# amigaDIP40_2025-07-20.net
KiCad netlist of a schematic drawn in Altium Designer
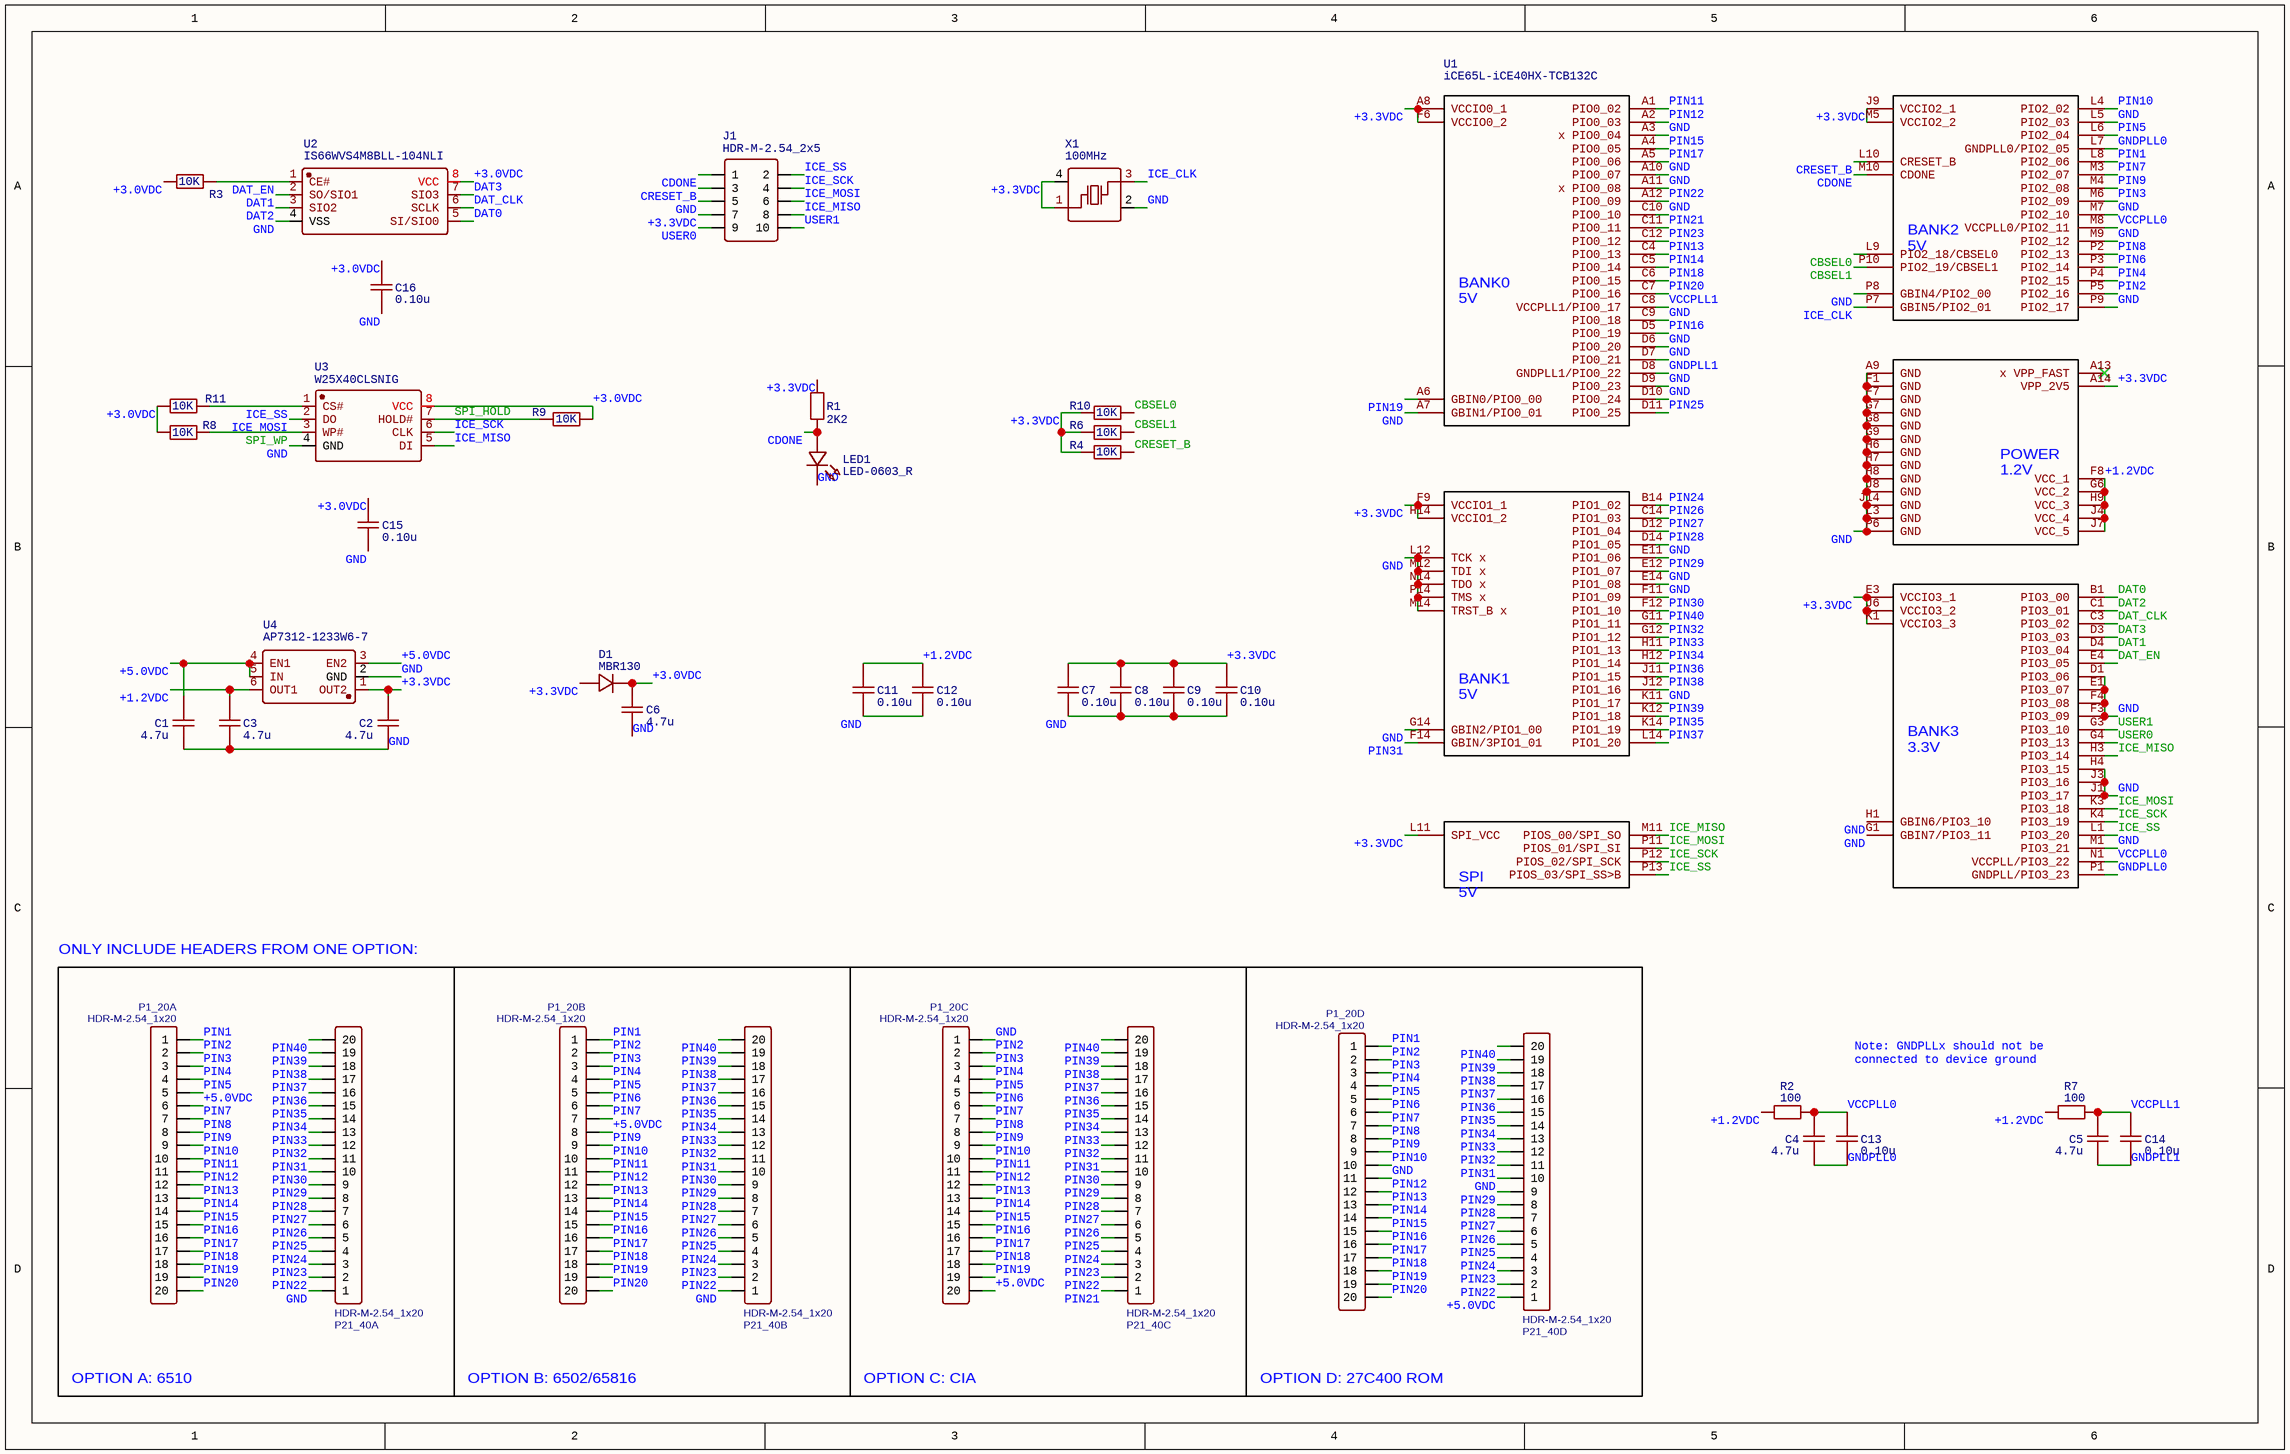
[diagram p0: amigaDIP40_2025-07-20.schdoc]

(export (version "E")
  (design (tool "Eeschema 10.0.6"))
  (components
    (comp (ref "C1")
      (value "4.7u")
      (fields
        (field (name "MANUFACTURER PART") "GCM21BR71E105KA56L")
        (field (name "MANUFACTURER") "MuRata")
        (field (name "CONTRIBUTOR") "LCEDA_Lib")
      )
      (libsource (lib "altium-import") (part "root_1_4.7u_"))
    )
    (comp (ref "C2")
      (value "4.7u")
      (fields
        (field (name "MANUFACTURER PART") "GCM21BR71E105KA56L")
        (field (name "MANUFACTURER") "MuRata")
        (field (name "CONTRIBUTOR") "LCEDA_Lib")
      )
      (libsource (lib "altium-import") (part "root_1_4.7u_"))
    )
    (comp (ref "C3")
      (value "4.7u")
      (fields
        (field (name "MANUFACTURER PART") "GCM21BR71E105KA56L")
        (field (name "MANUFACTURER") "MuRata")
        (field (name "CONTRIBUTOR") "LCEDA_Lib")
      )
      (libsource (lib "") (part "root_1_4.7u__1"))
    )
    (comp (ref "C4")
      (value "4.7u")
      (fields
        (field (name "MANUFACTURER PART") "GCM21BR71E105KA56L")
        (field (name "MANUFACTURER") "MuRata")
        (field (name "CONTRIBUTOR") "LCEDA_Lib")
      )
      (libsource (lib "altium-import") (part "root_1_4.7u_"))
    )
    (comp (ref "C5")
      (value "4.7u")
      (fields
        (field (name "MANUFACTURER PART") "GCM21BR71E105KA56L")
        (field (name "MANUFACTURER") "MuRata")
        (field (name "CONTRIBUTOR") "LCEDA_Lib")
      )
      (libsource (lib "altium-import") (part "root_1_4.7u_"))
    )
    (comp (ref "C6")
      (value "4.7u")
      (fields
        (field (name "MANUFACTURER PART") "GCM21BR71E105KA56L")
        (field (name "MANUFACTURER") "MuRata")
        (field (name "CONTRIBUTOR") "LCEDA_Lib")
      )
      (libsource (lib "") (part "root_1_4.7u__1"))
    )
    (comp (ref "C7")
      (value "0.10u")
      (fields
        (field (name "MANUFACTURER PART") "GRM188R71H104KA93D")
        (field (name "MANUFACTURER") "MuRata")
        (field (name "CONTRIBUTOR") "LCEDA_Lib")
      )
      (libsource (lib "altium-import") (part "root_1_0.10u_"))
    )
    (comp (ref "C8")
      (value "0.10u")
      (fields
        (field (name "MANUFACTURER PART") "GRM188R71H104KA93D")
        (field (name "MANUFACTURER") "MuRata")
        (field (name "CONTRIBUTOR") "LCEDA_Lib")
      )
      (libsource (lib "altium-import") (part "root_1_0.10u_"))
    )
    (comp (ref "C9")
      (value "0.10u")
      (fields
        (field (name "MANUFACTURER PART") "GRM188R71H104KA93D")
        (field (name "MANUFACTURER") "MuRata")
        (field (name "CONTRIBUTOR") "LCEDA_Lib")
      )
      (libsource (lib "altium-import") (part "root_1_0.10u_"))
    )
    (comp (ref "C10")
      (value "0.10u")
      (fields
        (field (name "MANUFACTURER PART") "GRM188R71H104KA93D")
        (field (name "MANUFACTURER") "MuRata")
        (field (name "CONTRIBUTOR") "LCEDA_Lib")
      )
      (libsource (lib "altium-import") (part "root_1_0.10u_"))
    )
    (comp (ref "C11")
      (value "0.10u")
      (fields
        (field (name "MANUFACTURER PART") "GRM188R71H104KA93D")
        (field (name "MANUFACTURER") "MuRata")
        (field (name "CONTRIBUTOR") "LCEDA_Lib")
      )
      (libsource (lib "altium-import") (part "root_1_0.10u_"))
    )
    (comp (ref "C12")
      (value "0.10u")
      (fields
        (field (name "MANUFACTURER PART") "GRM188R71H104KA93D")
        (field (name "MANUFACTURER") "MuRata")
        (field (name "CONTRIBUTOR") "LCEDA_Lib")
      )
      (libsource (lib "altium-import") (part "root_1_0.10u_"))
    )
    (comp (ref "C13")
      (value "0.10u")
      (fields
        (field (name "MANUFACTURER PART") "GRM188R71H104KA93D")
        (field (name "MANUFACTURER") "MuRata")
        (field (name "CONTRIBUTOR") "LCEDA_Lib")
      )
      (libsource (lib "altium-import") (part "root_1_0.10u_"))
    )
    (comp (ref "C14")
      (value "0.10u")
      (fields
        (field (name "MANUFACTURER PART") "GRM188R71H104KA93D")
        (field (name "MANUFACTURER") "MuRata")
        (field (name "CONTRIBUTOR") "LCEDA_Lib")
      )
      (libsource (lib "altium-import") (part "root_1_0.10u_"))
    )
    (comp (ref "C15")
      (value "0.10u")
      (fields
        (field (name "MANUFACTURER PART") "GRM188R71H104KA93D")
        (field (name "MANUFACTURER") "MuRata")
        (field (name "CONTRIBUTOR") "LCEDA_Lib")
      )
      (libsource (lib "altium-import") (part "root_1_0.10u_"))
    )
    (comp (ref "C16")
      (value "0.10u")
      (fields
        (field (name "MANUFACTURER PART") "GRM188R71H104KA93D")
        (field (name "MANUFACTURER") "MuRata")
        (field (name "CONTRIBUTOR") "LCEDA_Lib")
      )
      (libsource (lib "altium-import") (part "root_1_0.10u_"))
    )
    (comp (ref "D1")
      (value "MBR130")
      (fields (field (name "MANUFACTURER") "SK") (field (name "CONTRIBUTOR") "LCSC"))
      (libsource (lib "altium-import") (part "root_2_MBR130_"))
    )
    (comp (ref "J1")
      (value "HDR-M-2.54_2x5")
      (fields (field (name "CONTRIBUTOR") "LCEDA_Lib"))
      (libsource (lib "altium-import") (part "root_0_HDR-M-2.54_2x5_"))
    )
    (comp (ref "LED1")
      (value "LED-0603_R")
      (fields
        (field (name "MANUFACTURER") "EVERLIGHT(台湾亿光)")
        (field (name "MANUFACTURER PART") "19-217/R6C-AL1M2VY/3T")
        (field (name "CONTRIBUTOR") "LCEDA_01")
      )
      (libsource (lib "altium-import") (part "root_3_LED-0603_R_"))
    )
    (comp (ref "P1_20A")
      (value "HDR-M-2.54_1x20")
      (fields (field (name "CONTRIBUTOR") "LCEDA_Lib"))
      (libsource (lib "altium-import") (part "root_0_HDR-M-2.54_1x20_"))
    )
    (comp (ref "P1_20B")
      (value "HDR-M-2.54_1x20")
      (fields (field (name "CONTRIBUTOR") "LCEDA_Lib"))
      (libsource (lib "altium-import") (part "root_0_HDR-M-2.54_1x20_"))
    )
    (comp (ref "P1_20C")
      (value "HDR-M-2.54_1x20")
      (fields (field (name "CONTRIBUTOR") "LCEDA_Lib"))
      (libsource (lib "altium-import") (part "root_0_HDR-M-2.54_1x20_"))
    )
    (comp (ref "P1_20D")
      (value "HDR-M-2.54_1x20")
      (fields (field (name "CONTRIBUTOR") "LCEDA_Lib"))
      (libsource (lib "altium-import") (part "root_0_HDR-M-2.54_1x20_"))
    )
    (comp (ref "P21_40A")
      (value "HDR-M-2.54_1x20")
      (fields (field (name "CONTRIBUTOR") "LCEDA_Lib"))
      (libsource (lib "") (part "root_0_HDR-M-2.54_1x20__1"))
    )
    (comp (ref "P21_40B")
      (value "HDR-M-2.54_1x20")
      (fields (field (name "CONTRIBUTOR") "LCEDA_Lib"))
      (libsource (lib "") (part "root_0_HDR-M-2.54_1x20__1"))
    )
    (comp (ref "P21_40C")
      (value "HDR-M-2.54_1x20")
      (fields (field (name "CONTRIBUTOR") "LCEDA_Lib"))
      (libsource (lib "") (part "root_0_HDR-M-2.54_1x20__1"))
    )
    (comp (ref "P21_40D")
      (value "HDR-M-2.54_1x20")
      (fields (field (name "CONTRIBUTOR") "LCEDA_Lib"))
      (libsource (lib "") (part "root_0_HDR-M-2.54_1x20__1"))
    )
    (comp (ref "R1")
      (value "2K2")
      (fields
        (field (name "MANUFACTURER PART") "0402WGF1003TCE")
        (field (name "MANUFACTURER") "UniOhm")
        (field (name "CONTRIBUTOR") "LCEDA_Lib")
      )
      (libsource (lib "altium-import") (part "root_1_2K2_"))
    )
    (comp (ref "R2")
      (value "100")
      (fields (field (name "CONTRIBUTOR") "LCEDA_Lib"))
      (libsource (lib "altium-import") (part "root_0_100_"))
    )
    (comp (ref "R3")
      (value "10K")
      (fields
        (field (name "MANUFACTURER PART") "0402WGF1003TCE")
        (field (name "MANUFACTURER") "UniOhm")
        (field (name "CONTRIBUTOR") "LCEDA_Lib")
      )
      (libsource (lib "altium-import") (part "root_0_10K_"))
    )
    (comp (ref "R4")
      (value "10K")
      (fields
        (field (name "MANUFACTURER PART") "0402WGF1003TCE")
        (field (name "MANUFACTURER") "UniOhm")
        (field (name "CONTRIBUTOR") "LCEDA_Lib")
      )
      (libsource (lib "altium-import") (part "root_0_10K_"))
    )
    (comp (ref "R6")
      (value "10K")
      (fields
        (field (name "MANUFACTURER PART") "0402WGF1003TCE")
        (field (name "MANUFACTURER") "UniOhm")
        (field (name "CONTRIBUTOR") "LCEDA_Lib")
      )
      (libsource (lib "altium-import") (part "root_0_10K_"))
    )
    (comp (ref "R7")
      (value "100")
      (fields (field (name "CONTRIBUTOR") "LCEDA_Lib"))
      (libsource (lib "altium-import") (part "root_0_100_"))
    )
    (comp (ref "R8")
      (value "10K")
      (fields
        (field (name "MANUFACTURER PART") "0402WGF1003TCE")
        (field (name "MANUFACTURER") "UniOhm")
        (field (name "CONTRIBUTOR") "LCEDA_Lib")
      )
      (libsource (lib "altium-import") (part "root_0_10K_"))
    )
    (comp (ref "R9")
      (value "10K")
      (fields
        (field (name "MANUFACTURER PART") "0402WGF1003TCE")
        (field (name "MANUFACTURER") "UniOhm")
        (field (name "CONTRIBUTOR") "LCEDA_Lib")
      )
      (libsource (lib "") (part "root_0_10K__1"))
    )
    (comp (ref "R10")
      (value "10K")
      (fields
        (field (name "MANUFACTURER PART") "0402WGF1003TCE")
        (field (name "MANUFACTURER") "UniOhm")
        (field (name "CONTRIBUTOR") "LCEDA_Lib")
      )
      (libsource (lib "altium-import") (part "root_0_10K_"))
    )
    (comp (ref "R11")
      (value "10K")
      (fields
        (field (name "MANUFACTURER PART") "0402WGF1003TCE")
        (field (name "MANUFACTURER") "UniOhm")
        (field (name "CONTRIBUTOR") "LCEDA_Lib")
      )
      (libsource (lib "altium-import") (part "root_0_10K_"))
    )
    (comp (ref "U1")
      (value "iCE65L-iCE40HX-TCB132C")
      (fields
        (field (name "MANUFACTURER") "Lattice")
        (field (name "MANUFACTURER PART") "ICE65L04F-TCB132C")
        (field (name "CONTRIBUTOR") "Renee")
      )
      (libsource (lib "altium-import") (part "root_0_iCE65L-iCE40HX-TCB132C_"))
    )
    (comp (ref "U2")
      (value "IS66WVS4M8BLL-104NLI")
      (fields (field (name "MANUFACTURER PART") "ESP-PSRAM64H") (field (name "CONTRIBUTOR") "LCSC"))
      (libsource (lib "altium-import") (part "root_0_IS66WVS4M8BLL-104NLI_"))
    )
    (comp (ref "U3")
      (value "W25X40CLSNIG")
      (fields (field (name "MANUFACTURER") "WINBOND"))
      (libsource (lib "altium-import") (part "root_0_W25X40CLSNIG_"))
    )
    (comp (ref "U4")
      (value "AP7312-1233W6-7")
      (fields
        (field (name "MANUFACTURER") "DIODES(美台)")
        (field (name "MANUFACTURER PART") "AP7312-1828W6-7")
        (field (name "CONTRIBUTOR") "lcsc")
      )
      (libsource (lib "altium-import") (part "root_2_AP7312-1233W6-7_"))
    )
    (comp (ref "X1")
      (value "100MHz")
      (fields
        (field (name "MANUFACTURER") "TAITIEN Elec")
        (field (name "MANUFACTURER PART") "OXETDLJTNF-100.000000MHZ")
        (field (name "CONTRIBUTOR") "LCSC")
      )
      (libsource (lib "altium-import") (part "root_0_100MHz_"))
    )
  )
  (nets
    (net (code "1") (name "/+1.2VDC") (class "Default")
      (node (ref "C11") (pin "2") (pinfunction "2_2") (pintype "passive"))
      (node (ref "C12") (pin "2") (pinfunction "2_2") (pintype "passive"))
      (node (ref "C3") (pin "2") (pinfunction "2_2") (pintype "passive"))
      (node (ref "R2") (pin "1") (pinfunction "1_1") (pintype "passive"))
      (node (ref "R7") (pin "1") (pinfunction "1_1") (pintype "passive"))
      (node (ref "U1") (pin "F8") (pinfunction "VCC_1_F8") (pintype "passive"))
      (node (ref "U1") (pin "G6") (pinfunction "VCC_2_G6") (pintype "passive"))
      (node (ref "U1") (pin "H9") (pinfunction "VCC_3_H9") (pintype "passive"))
      (node (ref "U1") (pin "J4") (pinfunction "VCC_4_J4") (pintype "passive"))
      (node (ref "U1") (pin "J7") (pinfunction "VCC_5_J7") (pintype "passive"))
      (node (ref "U4") (pin "6") (pinfunction "OUT1_6") (pintype "passive"))
    )
    (net (code "2") (name "/+3.0VDC") (class "Default")
      (node (ref "C15") (pin "2") (pinfunction "2_2") (pintype "passive"))
      (node (ref "C16") (pin "2") (pinfunction "2_2") (pintype "passive"))
      (node (ref "C6") (pin "2") (pinfunction "2_2") (pintype "passive"))
      (node (ref "D1") (pin "1") (pinfunction "C_1") (pintype "passive"))
      (node (ref "R11") (pin "1") (pinfunction "1_1") (pintype "passive"))
      (node (ref "R3") (pin "1") (pinfunction "1_1") (pintype "passive"))
      (node (ref "R8") (pin "1") (pinfunction "1_1") (pintype "passive"))
      (node (ref "R9") (pin "1") (pinfunction "1_1") (pintype "passive"))
      (node (ref "U2") (pin "8") (pinfunction "VCC_8") (pintype "passive"))
      (node (ref "U3") (pin "8") (pinfunction "VCC_8") (pintype "passive"))
    )
    (net (code "3") (name "/+3.3VDC") (class "Default")
      (node (ref "C10") (pin "2") (pinfunction "2_2") (pintype "passive"))
      (node (ref "C2") (pin "2") (pinfunction "2_2") (pintype "passive"))
      (node (ref "C7") (pin "2") (pinfunction "2_2") (pintype "passive"))
      (node (ref "C8") (pin "2") (pinfunction "2_2") (pintype "passive"))
      (node (ref "C9") (pin "2") (pinfunction "2_2") (pintype "passive"))
      (node (ref "D1") (pin "2") (pinfunction "A_2") (pintype "passive"))
      (node (ref "J1") (pin "7") (pinfunction "7_7") (pintype "passive"))
      (node (ref "R1") (pin "2") (pinfunction "2_2") (pintype "passive"))
      (node (ref "R10") (pin "1") (pinfunction "1_1") (pintype "passive"))
      (node (ref "R4") (pin "1") (pinfunction "1_1") (pintype "passive"))
      (node (ref "R6") (pin "1") (pinfunction "1_1") (pintype "passive"))
      (node (ref "U1") (pin "A14") (pinfunction "VPP_2V5_A14") (pintype "passive"))
      (node (ref "U1") (pin "A8") (pinfunction "VCCIO0_1_A8") (pintype "passive"))
      (node (ref "U1") (pin "E3") (pinfunction "VCCIO3_1_E3") (pintype "passive"))
      (node (ref "U1") (pin "F6") (pinfunction "VCCIO0_2_F6") (pintype "passive"))
      (node (ref "U1") (pin "F9") (pinfunction "VCCIO1_1_F9") (pintype "passive"))
      (node (ref "U1") (pin "H14") (pinfunction "VCCIO1_2_H14") (pintype "passive"))
      (node (ref "U1") (pin "J6") (pinfunction "VCCIO3_2_J6") (pintype "passive"))
      (node (ref "U1") (pin "J9") (pinfunction "VCCIO2_1_J9") (pintype "passive"))
      (node (ref "U1") (pin "K1") (pinfunction "VCCIO3_3_K1") (pintype "passive"))
      (node (ref "U1") (pin "L11") (pinfunction "SPI_VCC_L11") (pintype "passive"))
      (node (ref "U1") (pin "M5") (pinfunction "VCCIO2_2_M5") (pintype "passive"))
      (node (ref "U4") (pin "1") (pinfunction "OUT2_1") (pintype "passive"))
      (node (ref "X1") (pin "1") (pinfunction "OSC1_1") (pintype "passive"))
      (node (ref "X1") (pin "4") (pinfunction "GND_4") (pintype "passive"))
    )
    (net (code "4") (name "/+5.0VDC") (class "Default")
      (node (ref "C1") (pin "2") (pinfunction "2_2") (pintype "passive"))
      (node (ref "P1_20A") (pin "6") (pinfunction "6_6") (pintype "passive"))
      (node (ref "P1_20B") (pin "8") (pinfunction "8_8") (pintype "passive"))
      (node (ref "P1_20C") (pin "20") (pinfunction "20_20") (pintype "passive"))
      (node (ref "P21_40D") (pin "1") (pinfunction "1_1") (pintype "passive"))
      (node (ref "U4") (pin "3") (pinfunction "EN2_3") (pintype "passive"))
      (node (ref "U4") (pin "4") (pinfunction "EN1_4") (pintype "passive"))
      (node (ref "U4") (pin "5") (pinfunction "IN_5") (pintype "passive"))
    )
    (net (code "5") (name "/CBSEL0") (class "Default")
      (node (ref "R10") (pin "2") (pinfunction "2_2") (pintype "passive"))
      (node (ref "U1") (pin "L9") (pinfunction "PIO2_18/CBSEL0_L9") (pintype "passive"))
    )
    (net (code "6") (name "/CBSEL1") (class "Default")
      (node (ref "R6") (pin "2") (pinfunction "2_2") (pintype "passive"))
      (node (ref "U1") (pin "P10") (pinfunction "PIO2_19/CBSEL1_P10") (pintype "passive"))
    )
    (net (code "7") (name "/CDONE") (class "Default")
      (node (ref "J1") (pin "1") (pinfunction "1_1") (pintype "passive"))
      (node (ref "LED1") (pin "1") (pinfunction "1_1") (pintype "passive"))
      (node (ref "R1") (pin "1") (pinfunction "1_1") (pintype "passive"))
      (node (ref "U1") (pin "M10") (pinfunction "CDONE_M10") (pintype "passive"))
    )
    (net (code "8") (name "/CRESET_B") (class "Default")
      (node (ref "J1") (pin "3") (pinfunction "3_3") (pintype "passive"))
      (node (ref "R4") (pin "2") (pinfunction "2_2") (pintype "passive"))
      (node (ref "U1") (pin "L10") (pinfunction "CRESET_B_L10") (pintype "passive"))
    )
    (net (code "9") (name "/DAT0") (class "Default")
      (node (ref "U1") (pin "B1") (pinfunction "PIO3_00_B1") (pintype "passive"))
      (node (ref "U2") (pin "5") (pinfunction "SI/SIO0_5") (pintype "passive"))
    )
    (net (code "10") (name "/DAT1") (class "Default")
      (node (ref "U1") (pin "D4") (pinfunction "PIO3_04_D4") (pintype "passive"))
      (node (ref "U2") (pin "2") (pinfunction "SO/SIO1_2") (pintype "passive"))
    )
    (net (code "11") (name "/DAT2") (class "Default")
      (node (ref "U1") (pin "C1") (pinfunction "PIO3_01_C1") (pintype "passive"))
      (node (ref "U2") (pin "3") (pinfunction "SIO2_3") (pintype "passive"))
    )
    (net (code "12") (name "/DAT3") (class "Default")
      (node (ref "U1") (pin "D3") (pinfunction "PIO3_03_D3") (pintype "passive"))
      (node (ref "U2") (pin "7") (pinfunction "SIO3_7") (pintype "passive"))
    )
    (net (code "13") (name "/DAT_CLK") (class "Default")
      (node (ref "U1") (pin "C3") (pinfunction "PIO3_02_C3") (pintype "passive"))
      (node (ref "U2") (pin "6") (pinfunction "SCLK_6") (pintype "passive"))
    )
    (net (code "14") (name "/DAT_EN") (class "Default")
      (node (ref "R3") (pin "2") (pinfunction "2_2") (pintype "passive"))
      (node (ref "U1") (pin "E4") (pinfunction "PIO3_05_E4") (pintype "passive"))
      (node (ref "U2") (pin "1") (pinfunction "CE#_1") (pintype "passive"))
    )
    (net (code "15") (name "/GND") (class "Default")
      (node (ref "C1") (pin "1") (pinfunction "1_1") (pintype "passive"))
      (node (ref "C10") (pin "1") (pinfunction "1_1") (pintype "passive"))
      (node (ref "C11") (pin "1") (pinfunction "1_1") (pintype "passive"))
      (node (ref "C12") (pin "1") (pinfunction "1_1") (pintype "passive"))
      (node (ref "C15") (pin "1") (pinfunction "1_1") (pintype "passive"))
      (node (ref "C16") (pin "1") (pinfunction "1_1") (pintype "passive"))
      (node (ref "C2") (pin "1") (pinfunction "1_1") (pintype "passive"))
      (node (ref "C3") (pin "1") (pinfunction "1_1") (pintype "passive"))
      (node (ref "C6") (pin "1") (pinfunction "1_1") (pintype "passive"))
      (node (ref "C7") (pin "1") (pinfunction "1_1") (pintype "passive"))
      (node (ref "C8") (pin "1") (pinfunction "1_1") (pintype "passive"))
      (node (ref "C9") (pin "1") (pinfunction "1_1") (pintype "passive"))
      (node (ref "J1") (pin "5") (pinfunction "5_5") (pintype "passive"))
      (node (ref "LED1") (pin "2") (pinfunction "2_2") (pintype "passive"))
      (node (ref "P1_20C") (pin "1") (pinfunction "1_1") (pintype "passive"))
      (node (ref "P1_20D") (pin "11") (pinfunction "11_11") (pintype "passive"))
      (node (ref "P21_40A") (pin "1") (pinfunction "1_1") (pintype "passive"))
      (node (ref "P21_40B") (pin "1") (pinfunction "1_1") (pintype "passive"))
      (node (ref "P21_40D") (pin "10") (pinfunction "10_10") (pintype "passive"))
      (node (ref "U1") (pin "A10") (pinfunction "PIO0_07_A10") (pintype "passive"))
      (node (ref "U1") (pin "A11") (pinfunction "x_PIO0_08_A11") (pintype "passive"))
      (node (ref "U1") (pin "A3") (pinfunction "x_PIO0_04_A3") (pintype "passive"))
      (node (ref "U1") (pin "A7") (pinfunction "GBIN1/PIO0_01_A7") (pintype "passive"))
      (node (ref "U1") (pin "A9") (pinfunction "GND_A9") (pintype "passive"))
      (node (ref "U1") (pin "C10") (pinfunction "PIO0_10_C10") (pintype "passive"))
      (node (ref "U1") (pin "C9") (pinfunction "PIO0_18_C9") (pintype "passive"))
      (node (ref "U1") (pin "D1") (pinfunction "PIO3_06_D1") (pintype "passive"))
      (node (ref "U1") (pin "D10") (pinfunction "PIO0_24_D10") (pintype "passive"))
      (node (ref "U1") (pin "D6") (pinfunction "PIO0_20_D6") (pintype "passive"))
      (node (ref "U1") (pin "D7") (pinfunction "PIO0_21_D7") (pintype "passive"))
      (node (ref "U1") (pin "D9") (pinfunction "PIO0_23_D9") (pintype "passive"))
      (node (ref "U1") (pin "E1") (pinfunction "PIO3_07_E1") (pintype "passive"))
      (node (ref "U1") (pin "E11") (pinfunction "PIO1_06_E11") (pintype "passive"))
      (node (ref "U1") (pin "E14") (pinfunction "PIO1_08_E14") (pintype "passive"))
      (node (ref "U1") (pin "F1") (pinfunction "GND_F1") (pintype "passive"))
      (node (ref "U1") (pin "F11") (pinfunction "PIO1_09_F11") (pintype "passive"))
      (node (ref "U1") (pin "F3") (pinfunction "PIO3_09_F3") (pintype "passive"))
      (node (ref "U1") (pin "F4") (pinfunction "PIO3_08_F4") (pintype "passive"))
      (node (ref "U1") (pin "F7") (pinfunction "GND_F7") (pintype "passive"))
      (node (ref "U1") (pin "G1") (pinfunction "GBIN7/PIO3_11_G1") (pintype "passive"))
      (node (ref "U1") (pin "G14") (pinfunction "GBIN2/PIO1_00_G14") (pintype "passive"))
      (node (ref "U1") (pin "G7") (pinfunction "GND_G7") (pintype "passive"))
      (node (ref "U1") (pin "G8") (pinfunction "GND_G8") (pintype "passive"))
      (node (ref "U1") (pin "G9") (pinfunction "GND_G9") (pintype "passive"))
      (node (ref "U1") (pin "H1") (pinfunction "GBIN6/PIO3_10_H1") (pintype "passive"))
      (node (ref "U1") (pin "H4") (pinfunction "PIO3_15_H4") (pintype "passive"))
      (node (ref "U1") (pin "H6") (pinfunction "GND_H6") (pintype "passive"))
      (node (ref "U1") (pin "H7") (pinfunction "GND_H7") (pintype "passive"))
      (node (ref "U1") (pin "H8") (pinfunction "GND_H8") (pintype "passive"))
      (node (ref "U1") (pin "J1") (pinfunction "PIO3_17_J1") (pintype "passive"))
      (node (ref "U1") (pin "J14") (pinfunction "GND_J14") (pintype "passive"))
      (node (ref "U1") (pin "J3") (pinfunction "PIO3_16_J3") (pintype "passive"))
      (node (ref "U1") (pin "J8") (pinfunction "GND_J8") (pintype "passive"))
      (node (ref "U1") (pin "K11") (pinfunction "PIO1_17_K11") (pintype "passive"))
      (node (ref "U1") (pin "L12") (pinfunction "TCK_x_L12") (pintype "passive"))
      (node (ref "U1") (pin "L3") (pinfunction "GND_L3") (pintype "passive"))
      (node (ref "U1") (pin "L5") (pinfunction "PIO2_03_L5") (pintype "passive"))
      (node (ref "U1") (pin "M1") (pinfunction "PIO3_21_M1") (pintype "passive"))
      (node (ref "U1") (pin "M12") (pinfunction "TDI_x_M12") (pintype "passive"))
      (node (ref "U1") (pin "M14") (pinfunction "TRST_B_x_M14") (pintype "passive"))
      (node (ref "U1") (pin "M7") (pinfunction "PIO2_10_M7") (pintype "passive"))
      (node (ref "U1") (pin "M9") (pinfunction "PIO2_12_M9") (pintype "passive"))
      (node (ref "U1") (pin "N14") (pinfunction "TDO_x_N14") (pintype "passive"))
      (node (ref "U1") (pin "P14") (pinfunction "TMS_x_P14") (pintype "passive"))
      (node (ref "U1") (pin "P6") (pinfunction "GND_P6") (pintype "passive"))
      (node (ref "U1") (pin "P8") (pinfunction "GBIN4/PIO2_00_P8") (pintype "passive"))
      (node (ref "U1") (pin "P9") (pinfunction "PIO2_17_P9") (pintype "passive"))
      (node (ref "U2") (pin "4") (pinfunction "VSS_4") (pintype "passive"))
      (node (ref "U3") (pin "4") (pinfunction "GND_4") (pintype "passive"))
      (node (ref "U4") (pin "2") (pinfunction "GND_2") (pintype "passive"))
      (node (ref "X1") (pin "2") (pinfunction "GND_2") (pintype "passive"))
    )
    (net (code "16") (name "/GNDPLL0") (class "Default")
      (node (ref "C13") (pin "1") (pinfunction "1_1") (pintype "passive"))
      (node (ref "C4") (pin "1") (pinfunction "1_1") (pintype "passive"))
      (node (ref "U1") (pin "L7") (pinfunction "GNDPLL0/PIO2_05_L7") (pintype "passive"))
      (node (ref "U1") (pin "P1") (pinfunction "GNDPLL/PIO3_23_P1") (pintype "passive"))
    )
    (net (code "17") (name "/GNDPLL1") (class "Default")
      (node (ref "C14") (pin "1") (pinfunction "1_1") (pintype "passive"))
      (node (ref "C5") (pin "1") (pinfunction "1_1") (pintype "passive"))
      (node (ref "U1") (pin "D8") (pinfunction "GNDPLL1/PIO0_22_D8") (pintype "passive"))
    )
    (net (code "18") (name "/ICE_CLK") (class "Default")
      (node (ref "U1") (pin "P7") (pinfunction "GBIN5/PIO2_01_P7") (pintype "passive"))
      (node (ref "X1") (pin "3") (pinfunction "OSC2_3") (pintype "passive"))
    )
    (net (code "19") (name "/ICE_MISO") (class "Default")
      (node (ref "J1") (pin "8") (pinfunction "8_8") (pintype "passive"))
      (node (ref "U1") (pin "H3") (pinfunction "PIO3_14_H3") (pintype "passive"))
      (node (ref "U1") (pin "M11") (pinfunction "PIOS_00/SPI_SO_M11") (pintype "passive"))
      (node (ref "U3") (pin "5") (pinfunction "DI_5") (pintype "passive"))
    )
    (net (code "20") (name "/ICE_MOSI") (class "Default")
      (node (ref "J1") (pin "6") (pinfunction "6_6") (pintype "passive"))
      (node (ref "U1") (pin "K3") (pinfunction "PIO3_18_K3") (pintype "passive"))
      (node (ref "U1") (pin "P11") (pinfunction "PIOS_01/SPI_SI_P11") (pintype "passive"))
      (node (ref "U3") (pin "2") (pinfunction "DO_2") (pintype "passive"))
    )
    (net (code "21") (name "/ICE_SCK") (class "Default")
      (node (ref "J1") (pin "4") (pinfunction "4_4") (pintype "passive"))
      (node (ref "U1") (pin "K4") (pinfunction "PIO3_19_K4") (pintype "passive"))
      (node (ref "U1") (pin "P12") (pinfunction "PIOS_02/SPI_SCK_P12") (pintype "passive"))
      (node (ref "U3") (pin "6") (pinfunction "CLK_6") (pintype "passive"))
    )
    (net (code "22") (name "/ICE_SS") (class "Default")
      (node (ref "J1") (pin "2") (pinfunction "2_2") (pintype "passive"))
      (node (ref "R11") (pin "2") (pinfunction "2_2") (pintype "passive"))
      (node (ref "U1") (pin "L1") (pinfunction "PIO3_20_L1") (pintype "passive"))
      (node (ref "U1") (pin "P13") (pinfunction "PIOS_03/SPI_SS>B_P13") (pintype "passive"))
      (node (ref "U3") (pin "1") (pinfunction "CS#_1") (pintype "passive"))
    )
    (net (code "23") (name "/PIN1") (class "Default")
      (node (ref "P1_20A") (pin "1") (pinfunction "1_1") (pintype "passive"))
      (node (ref "P1_20B") (pin "1") (pinfunction "1_1") (pintype "passive"))
      (node (ref "P1_20D") (pin "1") (pinfunction "1_1") (pintype "passive"))
      (node (ref "U1") (pin "L8") (pinfunction "PIO2_06_L8") (pintype "passive"))
    )
    (net (code "24") (name "/PIN2") (class "Default")
      (node (ref "P1_20A") (pin "2") (pinfunction "2_2") (pintype "passive"))
      (node (ref "P1_20B") (pin "2") (pinfunction "2_2") (pintype "passive"))
      (node (ref "P1_20C") (pin "2") (pinfunction "2_2") (pintype "passive"))
      (node (ref "P1_20D") (pin "2") (pinfunction "2_2") (pintype "passive"))
      (node (ref "U1") (pin "P5") (pinfunction "PIO2_16_P5") (pintype "passive"))
    )
    (net (code "25") (name "/PIN3") (class "Default")
      (node (ref "P1_20A") (pin "3") (pinfunction "3_3") (pintype "passive"))
      (node (ref "P1_20B") (pin "3") (pinfunction "3_3") (pintype "passive"))
      (node (ref "P1_20C") (pin "3") (pinfunction "3_3") (pintype "passive"))
      (node (ref "P1_20D") (pin "3") (pinfunction "3_3") (pintype "passive"))
      (node (ref "U1") (pin "M6") (pinfunction "PIO2_09_M6") (pintype "passive"))
    )
    (net (code "26") (name "/PIN4") (class "Default")
      (node (ref "P1_20A") (pin "4") (pinfunction "4_4") (pintype "passive"))
      (node (ref "P1_20B") (pin "4") (pinfunction "4_4") (pintype "passive"))
      (node (ref "P1_20C") (pin "4") (pinfunction "4_4") (pintype "passive"))
      (node (ref "P1_20D") (pin "4") (pinfunction "4_4") (pintype "passive"))
      (node (ref "U1") (pin "P4") (pinfunction "PIO2_15_P4") (pintype "passive"))
    )
    (net (code "27") (name "/PIN5") (class "Default")
      (node (ref "P1_20A") (pin "5") (pinfunction "5_5") (pintype "passive"))
      (node (ref "P1_20B") (pin "5") (pinfunction "5_5") (pintype "passive"))
      (node (ref "P1_20C") (pin "5") (pinfunction "5_5") (pintype "passive"))
      (node (ref "P1_20D") (pin "5") (pinfunction "5_5") (pintype "passive"))
      (node (ref "U1") (pin "L6") (pinfunction "PIO2_04_L6") (pintype "passive"))
    )
    (net (code "28") (name "/PIN6") (class "Default")
      (node (ref "P1_20B") (pin "6") (pinfunction "6_6") (pintype "passive"))
      (node (ref "P1_20C") (pin "6") (pinfunction "6_6") (pintype "passive"))
      (node (ref "P1_20D") (pin "6") (pinfunction "6_6") (pintype "passive"))
      (node (ref "U1") (pin "P3") (pinfunction "PIO2_14_P3") (pintype "passive"))
    )
    (net (code "29") (name "/PIN7") (class "Default")
      (node (ref "P1_20A") (pin "7") (pinfunction "7_7") (pintype "passive"))
      (node (ref "P1_20B") (pin "7") (pinfunction "7_7") (pintype "passive"))
      (node (ref "P1_20C") (pin "7") (pinfunction "7_7") (pintype "passive"))
      (node (ref "P1_20D") (pin "7") (pinfunction "7_7") (pintype "passive"))
      (node (ref "U1") (pin "M3") (pinfunction "PIO2_07_M3") (pintype "passive"))
    )
    (net (code "30") (name "/PIN8") (class "Default")
      (node (ref "P1_20A") (pin "8") (pinfunction "8_8") (pintype "passive"))
      (node (ref "P1_20C") (pin "8") (pinfunction "8_8") (pintype "passive"))
      (node (ref "P1_20D") (pin "8") (pinfunction "8_8") (pintype "passive"))
      (node (ref "U1") (pin "P2") (pinfunction "PIO2_13_P2") (pintype "passive"))
    )
    (net (code "31") (name "/PIN9") (class "Default")
      (node (ref "P1_20A") (pin "9") (pinfunction "9_9") (pintype "passive"))
      (node (ref "P1_20B") (pin "9") (pinfunction "9_9") (pintype "passive"))
      (node (ref "P1_20C") (pin "9") (pinfunction "9_9") (pintype "passive"))
      (node (ref "P1_20D") (pin "9") (pinfunction "9_9") (pintype "passive"))
      (node (ref "U1") (pin "M4") (pinfunction "PIO2_08_M4") (pintype "passive"))
    )
    (net (code "32") (name "/PIN10") (class "Default")
      (node (ref "P1_20A") (pin "10") (pinfunction "10_10") (pintype "passive"))
      (node (ref "P1_20B") (pin "10") (pinfunction "10_10") (pintype "passive"))
      (node (ref "P1_20C") (pin "10") (pinfunction "10_10") (pintype "passive"))
      (node (ref "P1_20D") (pin "10") (pinfunction "10_10") (pintype "passive"))
      (node (ref "U1") (pin "L4") (pinfunction "PIO2_02_L4") (pintype "passive"))
    )
    (net (code "33") (name "/PIN11") (class "Default")
      (node (ref "P1_20A") (pin "11") (pinfunction "11_11") (pintype "passive"))
      (node (ref "P1_20B") (pin "11") (pinfunction "11_11") (pintype "passive"))
      (node (ref "P1_20C") (pin "11") (pinfunction "11_11") (pintype "passive"))
      (node (ref "U1") (pin "A1") (pinfunction "PIO0_02_A1") (pintype "passive"))
    )
    (net (code "34") (name "/PIN12") (class "Default")
      (node (ref "P1_20A") (pin "12") (pinfunction "12_12") (pintype "passive"))
      (node (ref "P1_20B") (pin "12") (pinfunction "12_12") (pintype "passive"))
      (node (ref "P1_20C") (pin "12") (pinfunction "12_12") (pintype "passive"))
      (node (ref "P1_20D") (pin "12") (pinfunction "12_12") (pintype "passive"))
      (node (ref "U1") (pin "A2") (pinfunction "PIO0_03_A2") (pintype "passive"))
    )
    (net (code "35") (name "/PIN13") (class "Default")
      (node (ref "P1_20A") (pin "13") (pinfunction "13_13") (pintype "passive"))
      (node (ref "P1_20B") (pin "13") (pinfunction "13_13") (pintype "passive"))
      (node (ref "P1_20C") (pin "13") (pinfunction "13_13") (pintype "passive"))
      (node (ref "P1_20D") (pin "13") (pinfunction "13_13") (pintype "passive"))
      (node (ref "U1") (pin "C4") (pinfunction "PIO0_13_C4") (pintype "passive"))
    )
    (net (code "36") (name "/PIN14") (class "Default")
      (node (ref "P1_20A") (pin "14") (pinfunction "14_14") (pintype "passive"))
      (node (ref "P1_20B") (pin "14") (pinfunction "14_14") (pintype "passive"))
      (node (ref "P1_20C") (pin "14") (pinfunction "14_14") (pintype "passive"))
      (node (ref "P1_20D") (pin "14") (pinfunction "14_14") (pintype "passive"))
      (node (ref "U1") (pin "C5") (pinfunction "PIO0_14_C5") (pintype "passive"))
    )
    (net (code "37") (name "/PIN15") (class "Default")
      (node (ref "P1_20A") (pin "15") (pinfunction "15_15") (pintype "passive"))
      (node (ref "P1_20B") (pin "15") (pinfunction "15_15") (pintype "passive"))
      (node (ref "P1_20C") (pin "15") (pinfunction "15_15") (pintype "passive"))
      (node (ref "P1_20D") (pin "15") (pinfunction "15_15") (pintype "passive"))
      (node (ref "U1") (pin "A4") (pinfunction "PIO0_05_A4") (pintype "passive"))
    )
    (net (code "38") (name "/PIN16") (class "Default")
      (node (ref "P1_20A") (pin "16") (pinfunction "16_16") (pintype "passive"))
      (node (ref "P1_20B") (pin "16") (pinfunction "16_16") (pintype "passive"))
      (node (ref "P1_20C") (pin "16") (pinfunction "16_16") (pintype "passive"))
      (node (ref "P1_20D") (pin "16") (pinfunction "16_16") (pintype "passive"))
      (node (ref "U1") (pin "D5") (pinfunction "PIO0_19_D5") (pintype "passive"))
    )
    (net (code "39") (name "/PIN17") (class "Default")
      (node (ref "P1_20A") (pin "17") (pinfunction "17_17") (pintype "passive"))
      (node (ref "P1_20B") (pin "17") (pinfunction "17_17") (pintype "passive"))
      (node (ref "P1_20C") (pin "17") (pinfunction "17_17") (pintype "passive"))
      (node (ref "P1_20D") (pin "17") (pinfunction "17_17") (pintype "passive"))
      (node (ref "U1") (pin "A5") (pinfunction "PIO0_06_A5") (pintype "passive"))
    )
    (net (code "40") (name "/PIN18") (class "Default")
      (node (ref "P1_20A") (pin "18") (pinfunction "18_18") (pintype "passive"))
      (node (ref "P1_20B") (pin "18") (pinfunction "18_18") (pintype "passive"))
      (node (ref "P1_20C") (pin "18") (pinfunction "18_18") (pintype "passive"))
      (node (ref "P1_20D") (pin "18") (pinfunction "18_18") (pintype "passive"))
      (node (ref "U1") (pin "C6") (pinfunction "PIO0_15_C6") (pintype "passive"))
    )
    (net (code "41") (name "/PIN19") (class "Default")
      (node (ref "P1_20A") (pin "19") (pinfunction "19_19") (pintype "passive"))
      (node (ref "P1_20B") (pin "19") (pinfunction "19_19") (pintype "passive"))
      (node (ref "P1_20C") (pin "19") (pinfunction "19_19") (pintype "passive"))
      (node (ref "P1_20D") (pin "19") (pinfunction "19_19") (pintype "passive"))
      (node (ref "U1") (pin "A6") (pinfunction "GBIN0/PIO0_00_A6") (pintype "passive"))
    )
    (net (code "42") (name "/PIN20") (class "Default")
      (node (ref "P1_20A") (pin "20") (pinfunction "20_20") (pintype "passive"))
      (node (ref "P1_20B") (pin "20") (pinfunction "20_20") (pintype "passive"))
      (node (ref "P1_20D") (pin "20") (pinfunction "20_20") (pintype "passive"))
      (node (ref "U1") (pin "C7") (pinfunction "PIO0_16_C7") (pintype "passive"))
    )
    (net (code "43") (name "/PIN21") (class "Default")
      (node (ref "P21_40C") (pin "1") (pinfunction "1_1") (pintype "passive"))
      (node (ref "U1") (pin "C11") (pinfunction "PIO0_11_C11") (pintype "passive"))
    )
    (net (code "44") (name "/PIN22") (class "Default")
      (node (ref "P21_40A") (pin "2") (pinfunction "2_2") (pintype "passive"))
      (node (ref "P21_40B") (pin "2") (pinfunction "2_2") (pintype "passive"))
      (node (ref "P21_40C") (pin "2") (pinfunction "2_2") (pintype "passive"))
      (node (ref "P21_40D") (pin "2") (pinfunction "2_2") (pintype "passive"))
      (node (ref "U1") (pin "A12") (pinfunction "PIO0_09_A12") (pintype "passive"))
    )
    (net (code "45") (name "/PIN23") (class "Default")
      (node (ref "P21_40A") (pin "3") (pinfunction "3_3") (pintype "passive"))
      (node (ref "P21_40B") (pin "3") (pinfunction "3_3") (pintype "passive"))
      (node (ref "P21_40C") (pin "3") (pinfunction "3_3") (pintype "passive"))
      (node (ref "P21_40D") (pin "3") (pinfunction "3_3") (pintype "passive"))
      (node (ref "U1") (pin "C12") (pinfunction "PIO0_12_C12") (pintype "passive"))
    )
    (net (code "46") (name "/PIN24") (class "Default")
      (node (ref "P21_40A") (pin "4") (pinfunction "4_4") (pintype "passive"))
      (node (ref "P21_40B") (pin "4") (pinfunction "4_4") (pintype "passive"))
      (node (ref "P21_40C") (pin "4") (pinfunction "4_4") (pintype "passive"))
      (node (ref "P21_40D") (pin "4") (pinfunction "4_4") (pintype "passive"))
      (node (ref "U1") (pin "B14") (pinfunction "PIO1_02_B14") (pintype "passive"))
    )
    (net (code "47") (name "/PIN25") (class "Default")
      (node (ref "P21_40A") (pin "5") (pinfunction "5_5") (pintype "passive"))
      (node (ref "P21_40B") (pin "5") (pinfunction "5_5") (pintype "passive"))
      (node (ref "P21_40C") (pin "5") (pinfunction "5_5") (pintype "passive"))
      (node (ref "P21_40D") (pin "5") (pinfunction "5_5") (pintype "passive"))
      (node (ref "U1") (pin "D11") (pinfunction "PIO0_25_D11") (pintype "passive"))
    )
    (net (code "48") (name "/PIN26") (class "Default")
      (node (ref "P21_40A") (pin "6") (pinfunction "6_6") (pintype "passive"))
      (node (ref "P21_40B") (pin "6") (pinfunction "6_6") (pintype "passive"))
      (node (ref "P21_40C") (pin "6") (pinfunction "6_6") (pintype "passive"))
      (node (ref "P21_40D") (pin "6") (pinfunction "6_6") (pintype "passive"))
      (node (ref "U1") (pin "C14") (pinfunction "PIO1_03_C14") (pintype "passive"))
    )
    (net (code "49") (name "/PIN27") (class "Default")
      (node (ref "P21_40A") (pin "7") (pinfunction "7_7") (pintype "passive"))
      (node (ref "P21_40B") (pin "7") (pinfunction "7_7") (pintype "passive"))
      (node (ref "P21_40C") (pin "7") (pinfunction "7_7") (pintype "passive"))
      (node (ref "P21_40D") (pin "7") (pinfunction "7_7") (pintype "passive"))
      (node (ref "U1") (pin "D12") (pinfunction "PIO1_04_D12") (pintype "passive"))
    )
    (net (code "50") (name "/PIN28") (class "Default")
      (node (ref "P21_40A") (pin "8") (pinfunction "8_8") (pintype "passive"))
      (node (ref "P21_40B") (pin "8") (pinfunction "8_8") (pintype "passive"))
      (node (ref "P21_40C") (pin "8") (pinfunction "8_8") (pintype "passive"))
      (node (ref "P21_40D") (pin "8") (pinfunction "8_8") (pintype "passive"))
      (node (ref "U1") (pin "D14") (pinfunction "PIO1_05_D14") (pintype "passive"))
    )
    (net (code "51") (name "/PIN29") (class "Default")
      (node (ref "P21_40A") (pin "9") (pinfunction "9_9") (pintype "passive"))
      (node (ref "P21_40B") (pin "9") (pinfunction "9_9") (pintype "passive"))
      (node (ref "P21_40C") (pin "9") (pinfunction "9_9") (pintype "passive"))
      (node (ref "P21_40D") (pin "9") (pinfunction "9_9") (pintype "passive"))
      (node (ref "U1") (pin "E12") (pinfunction "PIO1_07_E12") (pintype "passive"))
    )
    (net (code "52") (name "/PIN30") (class "Default")
      (node (ref "P21_40A") (pin "10") (pinfunction "10_10") (pintype "passive"))
      (node (ref "P21_40B") (pin "10") (pinfunction "10_10") (pintype "passive"))
      (node (ref "P21_40C") (pin "10") (pinfunction "10_10") (pintype "passive"))
      (node (ref "U1") (pin "F12") (pinfunction "PIO1_10_F12") (pintype "passive"))
    )
    (net (code "53") (name "/PIN31") (class "Default")
      (node (ref "P21_40A") (pin "11") (pinfunction "11_11") (pintype "passive"))
      (node (ref "P21_40B") (pin "11") (pinfunction "11_11") (pintype "passive"))
      (node (ref "P21_40C") (pin "11") (pinfunction "11_11") (pintype "passive"))
      (node (ref "P21_40D") (pin "11") (pinfunction "11_11") (pintype "passive"))
      (node (ref "U1") (pin "F14") (pinfunction "GBIN/3PIO1_01_F14") (pintype "passive"))
    )
    (net (code "54") (name "/PIN32") (class "Default")
      (node (ref "P21_40A") (pin "12") (pinfunction "12_12") (pintype "passive"))
      (node (ref "P21_40B") (pin "12") (pinfunction "12_12") (pintype "passive"))
      (node (ref "P21_40C") (pin "12") (pinfunction "12_12") (pintype "passive"))
      (node (ref "P21_40D") (pin "12") (pinfunction "12_12") (pintype "passive"))
      (node (ref "U1") (pin "G12") (pinfunction "PIO1_12_G12") (pintype "passive"))
    )
    (net (code "55") (name "/PIN33") (class "Default")
      (node (ref "P21_40A") (pin "13") (pinfunction "13_13") (pintype "passive"))
      (node (ref "P21_40B") (pin "13") (pinfunction "13_13") (pintype "passive"))
      (node (ref "P21_40C") (pin "13") (pinfunction "13_13") (pintype "passive"))
      (node (ref "P21_40D") (pin "13") (pinfunction "13_13") (pintype "passive"))
      (node (ref "U1") (pin "H11") (pinfunction "PIO1_13_H11") (pintype "passive"))
    )
    (net (code "56") (name "/PIN34") (class "Default")
      (node (ref "P21_40A") (pin "14") (pinfunction "14_14") (pintype "passive"))
      (node (ref "P21_40B") (pin "14") (pinfunction "14_14") (pintype "passive"))
      (node (ref "P21_40C") (pin "14") (pinfunction "14_14") (pintype "passive"))
      (node (ref "P21_40D") (pin "14") (pinfunction "14_14") (pintype "passive"))
      (node (ref "U1") (pin "H12") (pinfunction "PIO1_14_H12") (pintype "passive"))
    )
    (net (code "57") (name "/PIN35") (class "Default")
      (node (ref "P21_40A") (pin "15") (pinfunction "15_15") (pintype "passive"))
      (node (ref "P21_40B") (pin "15") (pinfunction "15_15") (pintype "passive"))
      (node (ref "P21_40C") (pin "15") (pinfunction "15_15") (pintype "passive"))
      (node (ref "P21_40D") (pin "15") (pinfunction "15_15") (pintype "passive"))
      (node (ref "U1") (pin "K14") (pinfunction "PIO1_19_K14") (pintype "passive"))
    )
    (net (code "58") (name "/PIN36") (class "Default")
      (node (ref "P21_40A") (pin "16") (pinfunction "16_16") (pintype "passive"))
      (node (ref "P21_40B") (pin "16") (pinfunction "16_16") (pintype "passive"))
      (node (ref "P21_40C") (pin "16") (pinfunction "16_16") (pintype "passive"))
      (node (ref "P21_40D") (pin "16") (pinfunction "16_16") (pintype "passive"))
      (node (ref "U1") (pin "J11") (pinfunction "PIO1_15_J11") (pintype "passive"))
    )
    (net (code "59") (name "/PIN37") (class "Default")
      (node (ref "P21_40A") (pin "17") (pinfunction "17_17") (pintype "passive"))
      (node (ref "P21_40B") (pin "17") (pinfunction "17_17") (pintype "passive"))
      (node (ref "P21_40C") (pin "17") (pinfunction "17_17") (pintype "passive"))
      (node (ref "P21_40D") (pin "17") (pinfunction "17_17") (pintype "passive"))
      (node (ref "U1") (pin "L14") (pinfunction "PIO1_20_L14") (pintype "passive"))
    )
    (net (code "60") (name "/PIN38") (class "Default")
      (node (ref "P21_40A") (pin "18") (pinfunction "18_18") (pintype "passive"))
      (node (ref "P21_40B") (pin "18") (pinfunction "18_18") (pintype "passive"))
      (node (ref "P21_40C") (pin "18") (pinfunction "18_18") (pintype "passive"))
      (node (ref "P21_40D") (pin "18") (pinfunction "18_18") (pintype "passive"))
      (node (ref "U1") (pin "J12") (pinfunction "PIO1_16_J12") (pintype "passive"))
    )
    (net (code "61") (name "/PIN39") (class "Default")
      (node (ref "P21_40A") (pin "19") (pinfunction "19_19") (pintype "passive"))
      (node (ref "P21_40B") (pin "19") (pinfunction "19_19") (pintype "passive"))
      (node (ref "P21_40C") (pin "19") (pinfunction "19_19") (pintype "passive"))
      (node (ref "P21_40D") (pin "19") (pinfunction "19_19") (pintype "passive"))
      (node (ref "U1") (pin "K12") (pinfunction "PIO1_18_K12") (pintype "passive"))
    )
    (net (code "62") (name "/PIN40") (class "Default")
      (node (ref "P21_40A") (pin "20") (pinfunction "20_20") (pintype "passive"))
      (node (ref "P21_40B") (pin "20") (pinfunction "20_20") (pintype "passive"))
      (node (ref "P21_40C") (pin "20") (pinfunction "20_20") (pintype "passive"))
      (node (ref "P21_40D") (pin "20") (pinfunction "20_20") (pintype "passive"))
      (node (ref "U1") (pin "G11") (pinfunction "PIO1_11_G11") (pintype "passive"))
    )
    (net (code "63") (name "/SPI_HOLD") (class "Default")
      (node (ref "R9") (pin "2") (pinfunction "2_2") (pintype "passive"))
      (node (ref "U3") (pin "7") (pinfunction "HOLD#_7") (pintype "passive"))
    )
    (net (code "64") (name "/SPI_WP") (class "Default")
      (node (ref "R8") (pin "2") (pinfunction "2_2") (pintype "passive"))
      (node (ref "U3") (pin "3") (pinfunction "WP#_3") (pintype "passive"))
    )
    (net (code "65") (name "/USER0") (class "Default")
      (node (ref "J1") (pin "9") (pinfunction "9_9") (pintype "passive"))
      (node (ref "U1") (pin "G4") (pinfunction "PIO3_13_G4") (pintype "passive"))
    )
    (net (code "66") (name "/USER1") (class "Default")
      (node (ref "J1") (pin "10") (pinfunction "10_10") (pintype "passive"))
      (node (ref "U1") (pin "G3") (pinfunction "PIO3_10_G3") (pintype "passive"))
    )
    (net (code "67") (name "/VCCPLL0") (class "Default")
      (node (ref "C13") (pin "2") (pinfunction "2_2") (pintype "passive"))
      (node (ref "C4") (pin "2") (pinfunction "2_2") (pintype "passive"))
      (node (ref "R2") (pin "2") (pinfunction "2_2") (pintype "passive"))
      (node (ref "U1") (pin "M8") (pinfunction "VCCPLL0/PIO2_11_M8") (pintype "passive"))
      (node (ref "U1") (pin "N1") (pinfunction "VCCPLL/PIO3_22_N1") (pintype "passive"))
    )
    (net (code "68") (name "/VCCPLL1") (class "Default")
      (node (ref "C14") (pin "2") (pinfunction "2_2") (pintype "passive"))
      (node (ref "C5") (pin "2") (pinfunction "2_2") (pintype "passive"))
      (node (ref "R7") (pin "2") (pinfunction "2_2") (pintype "passive"))
      (node (ref "U1") (pin "C8") (pinfunction "VCCPLL1/PIO0_17_C8") (pintype "passive"))
    )
    (net (code "69") (name "unconnected-(U1-x_VPP_FAST-PadA13)") (class "Default")
      (node (ref "U1") (pin "A13") (pinfunction "x_VPP_FAST_A13") (pintype "passive+no_connect"))
    )
  )
)
